# PCB-TLY-LAMP_v10-18.net
KiCad netlist of a schematic drawn in EAGLE
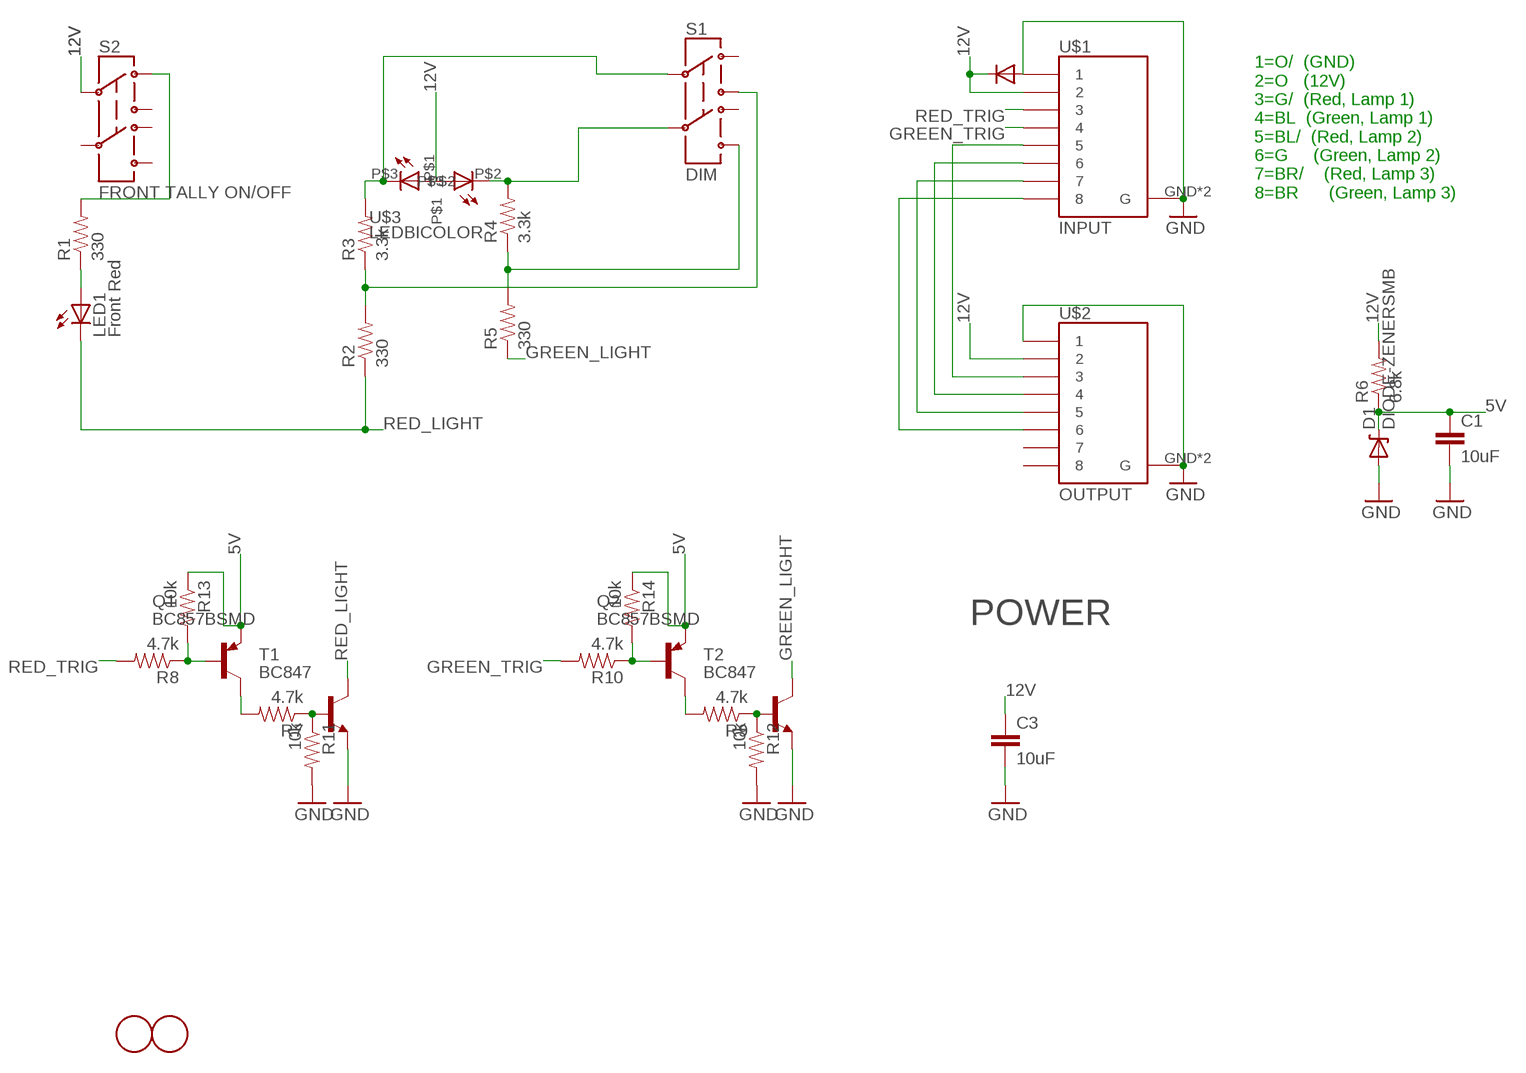
[diagram p0: schematic, sheet 1]

(export (version "E")
  (design (tool "Eeschema 10.0.6"))
  (components
    (comp (ref "C1")
      (value "10uF")
      (footprint "eagle-import:0805")
      (libsource (lib "eagle-import") (part "CAP0805"))
    )
    (comp (ref "C3")
      (value "10uF")
      (footprint "eagle-import:0805")
      (libsource (lib "eagle-import") (part "CAP0805"))
    )
    (comp (ref "D1")
      (value "DIODE-ZENERSMB")
      (footprint "eagle-import:SMB-DIODE")
      (libsource (lib "eagle-import") (part "DIODE-ZENERSMB"))
    )
    (comp (ref "LED1")
      (value "Front Red")
      (footprint "eagle-import:LED20")
      (libsource (lib "eagle-import") (part "LED20"))
    )
    (comp (ref "Q1")
      (value "BC857BSMD")
      (footprint "eagle-import:SOT23-BEC")
      (libsource (lib "eagle-import") (part "BC857SMDB"))
    )
    (comp (ref "Q2")
      (value "BC857BSMD")
      (footprint "eagle-import:SOT23-BEC")
      (libsource (lib "eagle-import") (part "BC857SMDB"))
    )
    (comp (ref "R1")
      (value "330")
      (footprint "eagle-import:0603-RES")
      (libsource (lib "eagle-import") (part "RESISTOR0603-RES"))
    )
    (comp (ref "R2")
      (value "330")
      (footprint "eagle-import:0603-RES")
      (libsource (lib "eagle-import") (part "RESISTOR0603-RES"))
    )
    (comp (ref "R3")
      (value "3.3k")
      (footprint "eagle-import:0603-RES")
      (libsource (lib "eagle-import") (part "RESISTOR0603-RES"))
    )
    (comp (ref "R4")
      (value "3.3k")
      (footprint "eagle-import:0603-RES")
      (libsource (lib "eagle-import") (part "RESISTOR0603-RES"))
    )
    (comp (ref "R5")
      (value "330")
      (footprint "eagle-import:0603-RES")
      (libsource (lib "eagle-import") (part "RESISTOR0603-RES"))
    )
    (comp (ref "R6")
      (value "6.8k")
      (footprint "eagle-import:0603-RES")
      (libsource (lib "eagle-import") (part "RESISTOR0603-RES"))
    )
    (comp (ref "R7")
      (value "4.7k")
      (footprint "eagle-import:0603-RES")
      (libsource (lib "eagle-import") (part "RESISTOR0603-RES"))
    )
    (comp (ref "R8")
      (value "4.7k")
      (footprint "eagle-import:0603-RES")
      (libsource (lib "eagle-import") (part "RESISTOR0603-RES"))
    )
    (comp (ref "R9")
      (value "4.7k")
      (footprint "eagle-import:0603-RES")
      (libsource (lib "eagle-import") (part "RESISTOR0603-RES"))
    )
    (comp (ref "R10")
      (value "4.7k")
      (footprint "eagle-import:0603-RES")
      (libsource (lib "eagle-import") (part "RESISTOR0603-RES"))
    )
    (comp (ref "R11")
      (value "10k")
      (footprint "eagle-import:0603-RES")
      (libsource (lib "eagle-import") (part "RESISTOR0603-RES"))
    )
    (comp (ref "R12")
      (value "10k")
      (footprint "eagle-import:0603-RES")
      (libsource (lib "eagle-import") (part "RESISTOR0603-RES"))
    )
    (comp (ref "R13")
      (value "10k")
      (footprint "eagle-import:0603-RES")
      (libsource (lib "eagle-import") (part "RESISTOR0603-RES"))
    )
    (comp (ref "R14")
      (value "10k")
      (footprint "eagle-import:0603-RES")
      (libsource (lib "eagle-import") (part "RESISTOR0603-RES"))
    )
    (comp (ref "S1")
      (value "DIM")
      (footprint "eagle-import:TECONNECTIVITY-DPDT")
      (libsource (lib "eagle-import") (part "SWITCH-DPDTPTH1"))
    )
    (comp (ref "S2")
      (value "FRONT TALLY ON/OFF")
      (footprint "eagle-import:TECONNECTIVITY-DPDT")
      (libsource (lib "eagle-import") (part "SWITCH-DPDTPTH1"))
    )
    (comp (ref "T1")
      (value "BC847")
      (footprint "eagle-import:SOT23")
      (libsource (lib "eagle-import") (part "BC847"))
    )
    (comp (ref "T2")
      (value "BC847")
      (footprint "eagle-import:SOT23")
      (libsource (lib "eagle-import") (part "BC847"))
    )
    (comp (ref "U$1")
      (value "INPUT")
      (footprint "eagle-import:RJ45-8_GND")
      (libsource (lib "eagle-import") (part "RJ45-8_GND"))
    )
    (comp (ref "U$2")
      (value "OUTPUT")
      (footprint "eagle-import:RJ45-8_GND")
      (libsource (lib "eagle-import") (part "RJ45-8_GND"))
    )
    (comp (ref "U$3")
      (value "LEDBICOLOR")
      (footprint "eagle-import:LEDBICOLOR")
      (libsource (lib "eagle-import") (part "LEDBICOLOR"))
    )
    (comp (ref "U$4")
      (value "FIDUCIAL")
      (footprint "eagle-import:FIDUCIAL_1MM")
      (libsource (lib "eagle-import") (part "FIDUCIAL"))
    )
    (comp (ref "U$5")
      (value "FIDUCIAL")
      (footprint "eagle-import:FIDUCIAL_1MM")
      (libsource (lib "eagle-import") (part "FIDUCIAL"))
    )
  )
  (nets
    (net (code "1") (name "/5V") (class "Default")
      (node (ref "C1") (pin "1") (pinfunction "1_1") (pintype "passive"))
      (node (ref "D1") (pin "C") (pinfunction "C_C") (pintype "passive"))
      (node (ref "Q1") (pin "E") (pinfunction "E_E") (pintype "passive"))
      (node (ref "Q2") (pin "E") (pinfunction "E_E") (pintype "passive"))
      (node (ref "R13") (pin "1") (pinfunction "1_1") (pintype "passive"))
      (node (ref "R14") (pin "1") (pinfunction "1_1") (pintype "passive"))
      (node (ref "R6") (pin "1") (pinfunction "1_1") (pintype "passive"))
    )
    (net (code "2") (name "/12V") (class "Default")
      (node (ref "C3") (pin "1") (pinfunction "1_1") (pintype "passive"))
      (node (ref "R6") (pin "2") (pinfunction "2_2") (pintype "passive"))
      (node (ref "S2") (pin "P$2") (pinfunction "2_P$2") (pintype "bidirectional"))
      (node (ref "U$1") (pin "2") (pinfunction "2_2") (pintype "bidirectional"))
      (node (ref "U$2") (pin "2") (pinfunction "2_2") (pintype "bidirectional"))
      (node (ref "U$3") (pin "P$1") (pinfunction "P$1_P$1") (pintype "bidirectional"))
    )
    (net (code "3") (name "/GREEN_LIGHT") (class "Default")
      (node (ref "R5") (pin "1") (pinfunction "1_1") (pintype "passive"))
      (node (ref "T2") (pin "3") (pinfunction "C_3") (pintype "passive"))
    )
    (net (code "4") (name "/GREEN_TRIG") (class "Default")
      (node (ref "R10") (pin "2") (pinfunction "2_2") (pintype "passive"))
      (node (ref "U$1") (pin "4") (pinfunction "4_4") (pintype "bidirectional"))
    )
    (net (code "5") (name "/RED_LIGHT") (class "Default")
      (node (ref "LED1") (pin "P$2") (pinfunction "C_P$2") (pintype "passive"))
      (node (ref "R2") (pin "1") (pinfunction "1_1") (pintype "passive"))
      (node (ref "T1") (pin "3") (pinfunction "C_3") (pintype "passive"))
    )
    (net (code "6") (name "/RED_TRIG") (class "Default")
      (node (ref "R8") (pin "2") (pinfunction "2_2") (pintype "passive"))
      (node (ref "U$1") (pin "3") (pinfunction "3_3") (pintype "bidirectional"))
    )
    (net (code "7") (name "GND") (class "Default")
      (node (ref "C1") (pin "2") (pinfunction "2_2") (pintype "passive"))
      (node (ref "C3") (pin "2") (pinfunction "2_2") (pintype "passive"))
      (node (ref "D1") (pin "A") (pinfunction "A_A") (pintype "passive"))
      (node (ref "R11") (pin "2") (pinfunction "2_2") (pintype "passive"))
      (node (ref "R12") (pin "2") (pinfunction "2_2") (pintype "passive"))
      (node (ref "T1") (pin "2") (pinfunction "E_2") (pintype "passive"))
      (node (ref "T2") (pin "2") (pinfunction "E_2") (pintype "passive"))
      (node (ref "U$1") (pin "1") (pinfunction "1_1") (pintype "bidirectional"))
      (node (ref "U$1") (pin "GND") (pinfunction "G_GND") (pintype "power_in"))
      (node (ref "U$1") (pin "GND1") (pinfunction "G_GND1") (pintype "power_in"))
      (node (ref "U$2") (pin "1") (pinfunction "1_1") (pintype "bidirectional"))
      (node (ref "U$2") (pin "GND") (pinfunction "G_GND") (pintype "power_in"))
      (node (ref "U$2") (pin "GND1") (pinfunction "G_GND1") (pintype "power_in"))
    )
    (net (code "8") (name "Net-(LED1-A)") (class "Default")
      (node (ref "LED1") (pin "P$1") (pinfunction "A_P$1") (pintype "passive"))
      (node (ref "R1") (pin "1") (pinfunction "1_1") (pintype "passive"))
    )
    (net (code "9") (name "Net-(Q1-PadB)") (class "Default")
      (node (ref "Q1") (pin "B") (pinfunction "B_B") (pintype "passive"))
      (node (ref "R13") (pin "2") (pinfunction "2_2") (pintype "passive"))
      (node (ref "R8") (pin "1") (pinfunction "1_1") (pintype "passive"))
    )
    (net (code "10") (name "Net-(Q1-PadC)") (class "Default")
      (node (ref "Q1") (pin "C") (pinfunction "C_C") (pintype "passive"))
      (node (ref "R7") (pin "2") (pinfunction "2_2") (pintype "passive"))
    )
    (net (code "11") (name "Net-(Q2-PadB)") (class "Default")
      (node (ref "Q2") (pin "B") (pinfunction "B_B") (pintype "passive"))
      (node (ref "R10") (pin "1") (pinfunction "1_1") (pintype "passive"))
      (node (ref "R14") (pin "2") (pinfunction "2_2") (pintype "passive"))
    )
    (net (code "12") (name "Net-(Q2-PadC)") (class "Default")
      (node (ref "Q2") (pin "C") (pinfunction "C_C") (pintype "passive"))
      (node (ref "R9") (pin "2") (pinfunction "2_2") (pintype "passive"))
    )
    (net (code "13") (name "Net-(S1-2)") (class "Default")
      (node (ref "R3") (pin "2") (pinfunction "2_2") (pintype "passive"))
      (node (ref "S1") (pin "P$2") (pinfunction "2_P$2") (pintype "bidirectional"))
      (node (ref "U$3") (pin "P$3") (pinfunction "P$3_P$3") (pintype "bidirectional"))
    )
    (net (code "14") (name "Net-(S1-3)") (class "Default")
      (node (ref "R2") (pin "2") (pinfunction "2_2") (pintype "passive"))
      (node (ref "R3") (pin "1") (pinfunction "1_1") (pintype "passive"))
      (node (ref "S1") (pin "P$3") (pinfunction "3_P$3") (pintype "bidirectional"))
    )
    (net (code "15") (name "Net-(S1-5)") (class "Default")
      (node (ref "R4") (pin "2") (pinfunction "2_2") (pintype "passive"))
      (node (ref "S1") (pin "P$5") (pinfunction "5_P$5") (pintype "bidirectional"))
      (node (ref "U$3") (pin "P$2") (pinfunction "P$2_P$2") (pintype "bidirectional"))
    )
    (net (code "16") (name "Net-(S1-6)") (class "Default")
      (node (ref "R4") (pin "1") (pinfunction "1_1") (pintype "passive"))
      (node (ref "R5") (pin "2") (pinfunction "2_2") (pintype "passive"))
      (node (ref "S1") (pin "P$6") (pinfunction "6_P$6") (pintype "bidirectional"))
    )
    (net (code "17") (name "Net-(S2-1)") (class "Default")
      (node (ref "R1") (pin "2") (pinfunction "2_2") (pintype "passive"))
      (node (ref "S2") (pin "P$1") (pinfunction "1_P$1") (pintype "bidirectional"))
    )
    (net (code "18") (name "Net-(T1-B)") (class "Default")
      (node (ref "R11") (pin "1") (pinfunction "1_1") (pintype "passive"))
      (node (ref "R7") (pin "1") (pinfunction "1_1") (pintype "passive"))
      (node (ref "T1") (pin "1") (pinfunction "B_1") (pintype "passive"))
    )
    (net (code "19") (name "Net-(T2-B)") (class "Default")
      (node (ref "R12") (pin "1") (pinfunction "1_1") (pintype "passive"))
      (node (ref "R9") (pin "1") (pinfunction "1_1") (pintype "passive"))
      (node (ref "T2") (pin "1") (pinfunction "B_1") (pintype "passive"))
    )
    (net (code "20") (name "Net-(U$1-Pad5)") (class "Default")
      (node (ref "U$1") (pin "5") (pinfunction "5_5") (pintype "bidirectional"))
      (node (ref "U$2") (pin "3") (pinfunction "3_3") (pintype "bidirectional"))
    )
    (net (code "21") (name "Net-(U$1-Pad6)") (class "Default")
      (node (ref "U$1") (pin "6") (pinfunction "6_6") (pintype "bidirectional"))
      (node (ref "U$2") (pin "4") (pinfunction "4_4") (pintype "bidirectional"))
    )
    (net (code "22") (name "Net-(U$1-Pad7)") (class "Default")
      (node (ref "U$1") (pin "7") (pinfunction "7_7") (pintype "bidirectional"))
      (node (ref "U$2") (pin "5") (pinfunction "5_5") (pintype "bidirectional"))
    )
    (net (code "23") (name "Net-(U$1-Pad8)") (class "Default")
      (node (ref "U$1") (pin "8") (pinfunction "8_8") (pintype "bidirectional"))
      (node (ref "U$2") (pin "6") (pinfunction "6_6") (pintype "bidirectional"))
    )
    (net (code "24") (name "unconnected-(S1-1-PadP$1)") (class "Default")
      (node (ref "S1") (pin "P$1") (pinfunction "1_P$1") (pintype "bidirectional"))
    )
    (net (code "25") (name "unconnected-(S1-4-PadP$4)") (class "Default")
      (node (ref "S1") (pin "P$4") (pinfunction "4_P$4") (pintype "bidirectional"))
    )
    (net (code "26") (name "unconnected-(S2-3-PadP$3)") (class "Default")
      (node (ref "S2") (pin "P$3") (pinfunction "3_P$3") (pintype "bidirectional"))
    )
    (net (code "27") (name "unconnected-(S2-4-PadP$4)") (class "Default")
      (node (ref "S2") (pin "P$4") (pinfunction "4_P$4") (pintype "bidirectional"))
    )
    (net (code "28") (name "unconnected-(S2-5-PadP$5)") (class "Default")
      (node (ref "S2") (pin "P$5") (pinfunction "5_P$5") (pintype "bidirectional"))
    )
    (net (code "29") (name "unconnected-(S2-6-PadP$6)") (class "Default")
      (node (ref "S2") (pin "P$6") (pinfunction "6_P$6") (pintype "bidirectional"))
    )
    (net (code "30") (name "unconnected-(U$2-Pad7)") (class "Default")
      (node (ref "U$2") (pin "7") (pinfunction "7_7") (pintype "bidirectional"))
    )
    (net (code "31") (name "unconnected-(U$2-Pad8)") (class "Default")
      (node (ref "U$2") (pin "8") (pinfunction "8_8") (pintype "bidirectional"))
    )
  )
)
